# STM32_microcontroller_power.net
KiCad netlist of a schematic drawn in Altium Designer
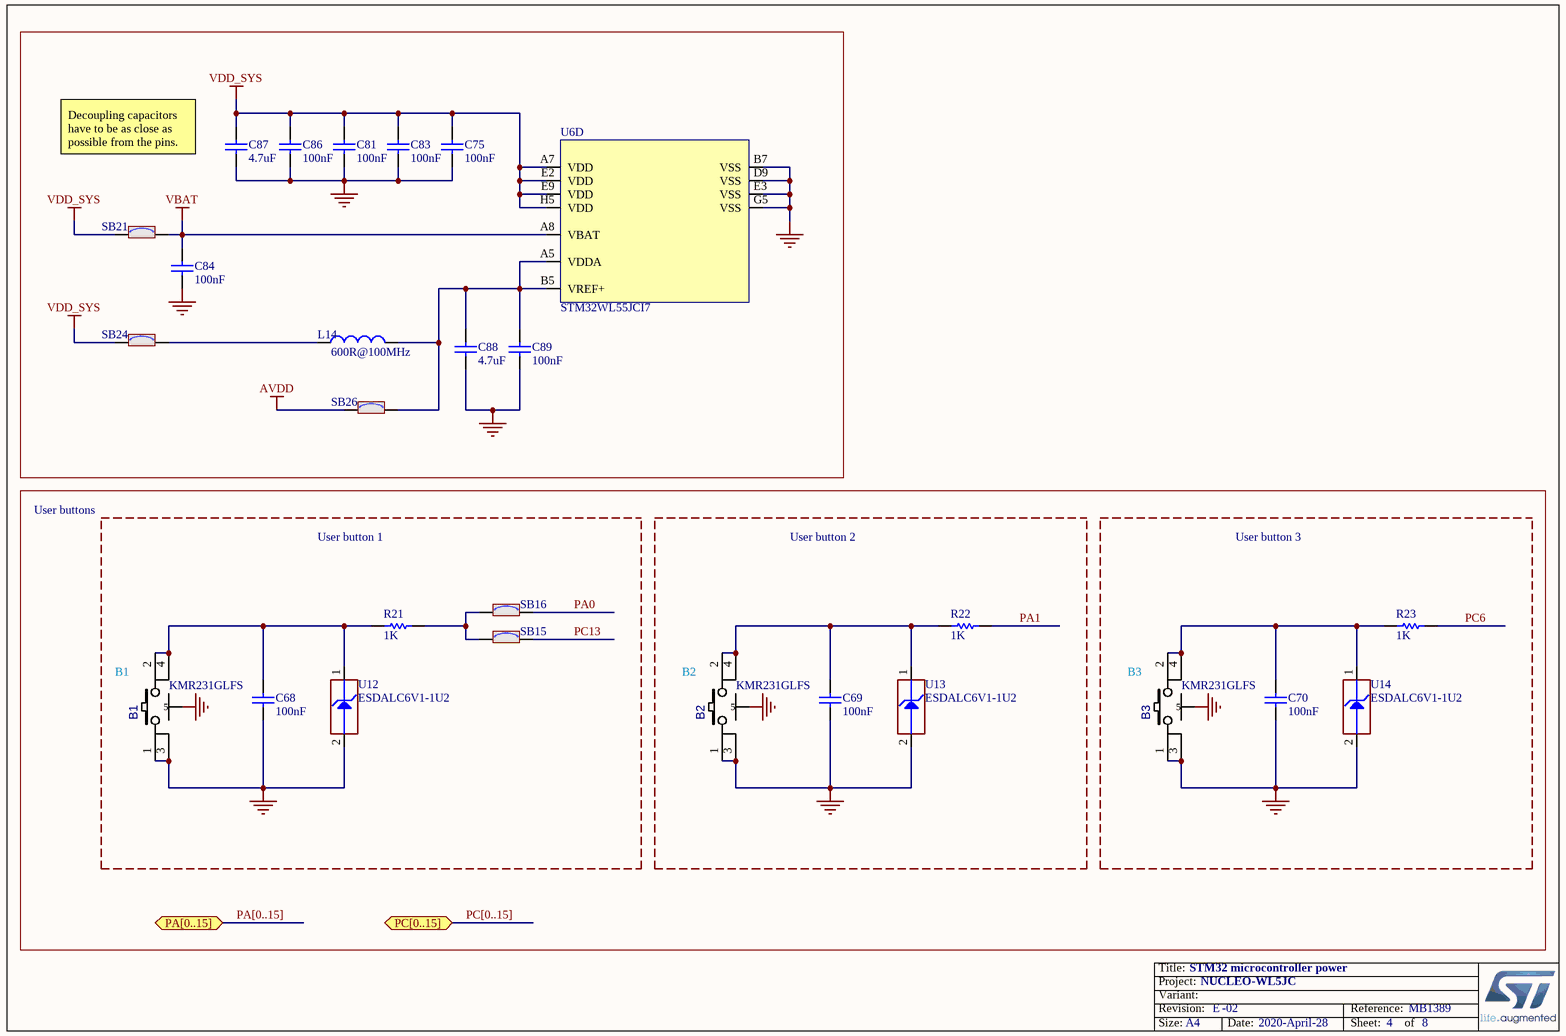
[diagram p0: STM32_microcontroller_power.SchDoc]

(export (version "E")
  (design (tool "Eeschema 10.0.6"))
  (components
    (comp (ref "B1")
      (value "KMR231GLFS")
      (footprint "SWI_C&K_Y78B23110FP__ITT_KMR231GLFS")
      (description "Microminiature Tact Switch for SMT - KMR 2 Series - 1.9 mm height")
      (fields
        (field (name "INTERNAL_PART_NUMBER") "MCD-01485")
        (field (name "MANUFACTURER") "C&K")
        (field (name "PROVIDED_BY") "SUBCO")
      )
      (libsource (lib "MCD_PARTS_database") (part "SW-PUSH-CMS_KMR2_BLACK"))
    )
    (comp (ref "B2")
      (value "KMR231GLFS")
      (footprint "SWI_C&K_Y78B23110FP__ITT_KMR231GLFS")
      (description "Microminiature Tact Switch for SMT - KMR 2 Series - 1.9 mm height")
      (fields
        (field (name "INTERNAL_PART_NUMBER") "MCD-01485")
        (field (name "MANUFACTURER") "C&K")
        (field (name "PROVIDED_BY") "SUBCO")
      )
      (libsource (lib "MCD_PARTS_database") (part "SW-PUSH-CMS_KMR2_BLACK"))
    )
    (comp (ref "B3")
      (value "KMR231GLFS")
      (footprint "SWI_C&K_Y78B23110FP__ITT_KMR231GLFS")
      (description "Microminiature Tact Switch for SMT - KMR 2 Series - 1.9 mm height")
      (fields
        (field (name "INTERNAL_PART_NUMBER") "MCD-01485")
        (field (name "MANUFACTURER") "C&K")
        (field (name "PROVIDED_BY") "SUBCO")
      )
      (libsource (lib "MCD_PARTS_database") (part "SW-PUSH-CMS_KMR2_BLACK"))
    )
    (comp (ref "C68")
      (value "100nF")
      (footprint "C0402")
      (description "Capacitor, MLCC, 100nF, 16V, X7R, 10%, 0402, T=0,5mm")
      (fields
        (field (name "INTERNAL_PART_NUMBER") "MCD-00102")
        (field (name "MANUFACTURER_PART_NUMBER") "CC0402KRX7R7BB104")
        (field (name "PROVIDED_BY") "SUBCO")
      )
      (libsource (lib "MCD_PARTS_database") (part "Capacitor"))
    )
    (comp (ref "C69")
      (value "100nF")
      (footprint "C0402")
      (description "Capacitor, MLCC, 100nF, 16V, X7R, 10%, 0402, T=0,5mm")
      (fields
        (field (name "INTERNAL_PART_NUMBER") "MCD-00102")
        (field (name "MANUFACTURER_PART_NUMBER") "CC0402KRX7R7BB104")
        (field (name "PROVIDED_BY") "SUBCO")
      )
      (libsource (lib "MCD_PARTS_database") (part "Capacitor"))
    )
    (comp (ref "C70")
      (value "100nF")
      (footprint "C0402")
      (description "Capacitor, MLCC, 100nF, 16V, X7R, 10%, 0402, T=0,5mm")
      (fields
        (field (name "INTERNAL_PART_NUMBER") "MCD-00102")
        (field (name "MANUFACTURER_PART_NUMBER") "CC0402KRX7R7BB104")
        (field (name "PROVIDED_BY") "SUBCO")
      )
      (libsource (lib "MCD_PARTS_database") (part "Capacitor"))
    )
    (comp (ref "C75")
      (value "100nF")
      (footprint "C0402")
      (description "Capacitor, MLCC, 100nF, 16V, X7R, 10%, 0402, T=0,5mm")
      (fields
        (field (name "INTERNAL_PART_NUMBER") "MCD-00102")
        (field (name "MANUFACTURER_PART_NUMBER") "CC0402KRX7R7BB104")
        (field (name "PROVIDED_BY") "SUBCO")
      )
      (libsource (lib "MCD_PARTS_database") (part "Capacitor"))
    )
    (comp (ref "C81")
      (value "100nF")
      (footprint "C0402")
      (description "Capacitor, MLCC, 100nF, 16V, X7R, 10%, 0402, T=0,5mm")
      (fields
        (field (name "INTERNAL_PART_NUMBER") "MCD-00102")
        (field (name "MANUFACTURER_PART_NUMBER") "CC0402KRX7R7BB104")
        (field (name "PROVIDED_BY") "SUBCO")
      )
      (libsource (lib "MCD_PARTS_database") (part "Capacitor"))
    )
    (comp (ref "C83")
      (value "100nF")
      (footprint "C0402")
      (description "Capacitor, MLCC, 100nF, 16V, X7R, 10%, 0402, T=0,5mm")
      (fields
        (field (name "INTERNAL_PART_NUMBER") "MCD-00102")
        (field (name "MANUFACTURER_PART_NUMBER") "CC0402KRX7R7BB104")
        (field (name "PROVIDED_BY") "SUBCO")
      )
      (libsource (lib "MCD_PARTS_database") (part "Capacitor"))
    )
    (comp (ref "C84")
      (value "100nF")
      (footprint "C0402")
      (description "Capacitor, MLCC, 100nF, 16V, X7R, 10%, 0402, T=0,5mm")
      (fields
        (field (name "INTERNAL_PART_NUMBER") "MCD-00102")
        (field (name "MANUFACTURER_PART_NUMBER") "CC0402KRX7R7BB104")
        (field (name "PROVIDED_BY") "SUBCO")
      )
      (libsource (lib "MCD_PARTS_database") (part "Capacitor"))
    )
    (comp (ref "C86")
      (value "100nF")
      (footprint "C0402")
      (description "Capacitor, MLCC, 100nF, 16V, X7R, 10%, 0402, T=0,5mm")
      (fields
        (field (name "INTERNAL_PART_NUMBER") "MCD-00102")
        (field (name "MANUFACTURER_PART_NUMBER") "CC0402KRX7R7BB104")
        (field (name "PROVIDED_BY") "SUBCO")
      )
      (libsource (lib "MCD_PARTS_database") (part "Capacitor"))
    )
    (comp (ref "C87")
      (value "4.7uF")
      (footprint "C0603")
      (description "Capacitor, MLCC, 4.7uF, 16V, X5R, 10%, 0603, T=0.8mm")
      (fields
        (field (name "INTERNAL_PART_NUMBER") "MCD-00009")
        (field (name "MANUFACTURER_PART_NUMBER") "CC0603KRX5R7BB475")
        (field (name "PROVIDED_BY") "SUBCO")
      )
      (libsource (lib "MCD_PARTS_database") (part "Capacitor"))
    )
    (comp (ref "C88")
      (value "4.7uF")
      (footprint "C0603")
      (description "Capacitor, MLCC, 4.7uF, 16V, X5R, 10%, 0603, T=0.8mm")
      (fields
        (field (name "INTERNAL_PART_NUMBER") "MCD-00009")
        (field (name "MANUFACTURER_PART_NUMBER") "CC0603KRX5R7BB475")
        (field (name "PROVIDED_BY") "SUBCO")
      )
      (libsource (lib "MCD_PARTS_database") (part "Capacitor"))
    )
    (comp (ref "C89")
      (value "100nF")
      (footprint "C0402")
      (description "Capacitor, MLCC, 100nF, 16V, X7R, 10%, 0402, T=0,5mm")
      (fields
        (field (name "INTERNAL_PART_NUMBER") "MCD-00102")
        (field (name "MANUFACTURER_PART_NUMBER") "CC0402KRX7R7BB104")
        (field (name "PROVIDED_BY") "SUBCO")
      )
      (libsource (lib "MCD_PARTS_database") (part "Capacitor"))
    )
    (comp (ref "L14")
      (value "600R@100MHz")
      (footprint "L0603")
      (description "SMD Chip ferrite bead, 600R@100MHz +/-25%, 350mA, 500mohm DC, 0603, T=0.8mm")
      (fields
        (field (name "INTERNAL_PART_NUMBER") "MCD-00047")
        (field (name "MANUFACTURER_PART_NUMBER") "FCM1608KF-601T03")
        (field (name "PROVIDED_BY") "SUBCO")
      )
      (libsource (lib "MCD_PARTS_database") (part "BEAD"))
    )
    (comp (ref "R21")
      (value "1K")
      (footprint "R0402")
      (description "Resistor,1K,0402,1%,1/16W")
      (fields
        (field (name "INTERNAL_PART_NUMBER") "MCD-00061")
        (field (name "MANUFACTURER_PART_NUMBER") "RC0402FR-071KL")
        (field (name "PROVIDED_BY") "SUBCO")
      )
      (libsource (lib "MCD_PARTS_database") (part "Resistor"))
    )
    (comp (ref "R22")
      (value "1K")
      (footprint "R0402")
      (description "Resistor,1K,0402,1%,1/16W")
      (fields
        (field (name "INTERNAL_PART_NUMBER") "MCD-00061")
        (field (name "MANUFACTURER_PART_NUMBER") "RC0402FR-071KL")
        (field (name "PROVIDED_BY") "SUBCO")
      )
      (libsource (lib "MCD_PARTS_database") (part "Resistor"))
    )
    (comp (ref "R23")
      (value "1K")
      (footprint "R0402")
      (description "Resistor,1K,0402,1%,1/16W")
      (fields
        (field (name "INTERNAL_PART_NUMBER") "MCD-00061")
        (field (name "MANUFACTURER_PART_NUMBER") "RC0402FR-071KL")
        (field (name "PROVIDED_BY") "SUBCO")
      )
      (libsource (lib "MCD_PARTS_database") (part "Resistor"))
    )
    (comp (ref "SB15")
      (value "~")
      (footprint "SOLDER-BRIDGE_R0603-0R")
      (description "Solder Bridge ON")
      (fields
        (field (name "INTERNAL_PART_NUMBER") "MCD-00071")
        (field (name "MANUFACTURER_PART_NUMBER") "RC0603JR-070RL")
        (field (name "PROVIDED_BY") "SUBCO")
      )
      (libsource (lib "MCD_PARTS_database") (part "SB_ON"))
    )
    (comp (ref "SB16")
      (value "~")
      (footprint "SOLDER-BRIDGE_R0603-0R")
      (description "Solder Bridge ON")
      (fields
        (field (name "INTERNAL_PART_NUMBER") "MCD-00071")
        (field (name "MANUFACTURER_PART_NUMBER") "RC0603JR-070RL")
        (field (name "PROVIDED_BY") "SUBCO")
      )
      (libsource (lib "MCD_PARTS_database") (part "SB_ON"))
    )
    (comp (ref "SB21")
      (value "~")
      (footprint "SOLDER-BRIDGE_R0603-0R")
      (description "Solder Bridge ON")
      (fields
        (field (name "INTERNAL_PART_NUMBER") "MCD-00071")
        (field (name "MANUFACTURER_PART_NUMBER") "RC0603JR-070RL")
        (field (name "PROVIDED_BY") "SUBCO")
      )
      (libsource (lib "MCD_PARTS_database") (part "SB_ON"))
    )
    (comp (ref "SB24")
      (value "~")
      (footprint "SOLDER-BRIDGE_R0603-0R")
      (description "Solder Bridge ON")
      (fields
        (field (name "INTERNAL_PART_NUMBER") "MCD-00071")
        (field (name "MANUFACTURER_PART_NUMBER") "RC0603JR-070RL")
        (field (name "PROVIDED_BY") "SUBCO")
      )
      (libsource (lib "MCD_PARTS_database") (part "SB_ON"))
    )
    (comp (ref "SB26")
      (value "~")
      (footprint "SOLDER-BRIDGE_R0603-0R")
      (description "Solder Bridge ON")
      (fields
        (field (name "INTERNAL_PART_NUMBER") "MCD-00071")
        (field (name "MANUFACTURER_PART_NUMBER") "RC0603JR-070RL")
        (field (name "PROVIDED_BY") "SUBCO")
      )
      (libsource (lib "MCD_PARTS_database") (part "SB_ON"))
    )
    (comp (ref "U6")
      (value "STM32WL55JCI7")
      (footprint "ICC_UFBGA73_5X5_P050")
      (description "Multiprotocol Wireless 32-bit MCUwith LPWAN Sub-GHz radio solution")
      (fields
        (field (name "INTERNAL_PART_NUMBER") "MCD-01435")
        (field (name "MANUFACTURER") "STMICROELECTRONICS")
      )
      (libsource (lib "MCD_PARTS_database") (part "STM32WL5x_BGA73"))
    )
    (comp (ref "U12")
      (value "ESDALC6V1-1U2")
      (footprint "ESD_ST0201")
      (description "ESD protection 6V1")
      (fields
        (field (name "INTERNAL_PART_NUMBER") "MCD-00170")
        (field (name "MANUFACTURER") "STMICROELECTRONICS")
        (field (name "PROVIDED_BY") "SUBCO with ST control")
      )
      (libsource (lib "MCD_PARTS_database") (part "ESD-TRANSIL"))
    )
    (comp (ref "U13")
      (value "ESDALC6V1-1U2")
      (footprint "ESD_ST0201")
      (description "ESD protection 6V1")
      (fields
        (field (name "INTERNAL_PART_NUMBER") "MCD-00170")
        (field (name "MANUFACTURER") "STMICROELECTRONICS")
        (field (name "PROVIDED_BY") "SUBCO with ST control")
      )
      (libsource (lib "MCD_PARTS_database") (part "ESD-TRANSIL"))
    )
    (comp (ref "U14")
      (value "ESDALC6V1-1U2")
      (footprint "ESD_ST0201")
      (description "ESD protection 6V1")
      (fields
        (field (name "INTERNAL_PART_NUMBER") "MCD-00170")
        (field (name "MANUFACTURER") "STMICROELECTRONICS")
        (field (name "PROVIDED_BY") "SUBCO with ST control")
      )
      (libsource (lib "MCD_PARTS_database") (part "ESD-TRANSIL"))
    )
  )
  (nets
    (net (code "29") (name "/PA0") (class "Default")
      (node (ref "SB16") (pin "2") (pinfunction "2_2") (pintype "passive"))
    )
    (net (code "30") (name "/PA1") (class "Default")
      (node (ref "R22") (pin "2") (pinfunction "2_2") (pintype "passive"))
    )
    (net (code "32") (name "/PC6") (class "Default")
      (node (ref "R23") (pin "2") (pinfunction "2_2") (pintype "passive"))
    )
    (net (code "33") (name "/PC13") (class "Default")
      (node (ref "SB15") (pin "2") (pinfunction "2_2") (pintype "passive"))
    )
    (net (code "35") (name "AVDD") (class "Default")
      (node (ref "SB26") (pin "1") (pinfunction "1_1") (pintype "passive"))
    )
    (net (code "36") (name "GND") (class "Default")
      (node (ref "B1") (pin "1") (pinfunction "1_1") (pintype "passive"))
      (node (ref "B1") (pin "3") (pinfunction "3_3") (pintype "passive"))
      (node (ref "B1") (pin "5") (pinfunction "5_5") (pintype "passive"))
      (node (ref "B2") (pin "1") (pinfunction "1_1") (pintype "passive"))
      (node (ref "B2") (pin "3") (pinfunction "3_3") (pintype "passive"))
      (node (ref "B2") (pin "5") (pinfunction "5_5") (pintype "passive"))
      (node (ref "B3") (pin "1") (pinfunction "1_1") (pintype "passive"))
      (node (ref "B3") (pin "3") (pinfunction "3_3") (pintype "passive"))
      (node (ref "B3") (pin "5") (pinfunction "5_5") (pintype "passive"))
      (node (ref "C68") (pin "1") (pinfunction "1_1") (pintype "passive"))
      (node (ref "C69") (pin "1") (pinfunction "1_1") (pintype "passive"))
      (node (ref "C70") (pin "1") (pinfunction "1_1") (pintype "passive"))
      (node (ref "C75") (pin "1") (pinfunction "1_1") (pintype "passive"))
      (node (ref "C81") (pin "1") (pinfunction "1_1") (pintype "passive"))
      (node (ref "C83") (pin "1") (pinfunction "1_1") (pintype "passive"))
      (node (ref "C84") (pin "1") (pinfunction "1_1") (pintype "passive"))
      (node (ref "C86") (pin "1") (pinfunction "1_1") (pintype "passive"))
      (node (ref "C87") (pin "1") (pinfunction "1_1") (pintype "passive"))
      (node (ref "C88") (pin "1") (pinfunction "1_1") (pintype "passive"))
      (node (ref "C89") (pin "1") (pinfunction "1_1") (pintype "passive"))
      (node (ref "U12") (pin "2") (pinfunction "GND_2") (pintype "passive"))
      (node (ref "U13") (pin "2") (pinfunction "GND_2") (pintype "passive"))
      (node (ref "U14") (pin "2") (pinfunction "GND_2") (pintype "passive"))
      (node (ref "U6") (pin "B7") (pinfunction "VSS_B7") (pintype "passive"))
      (node (ref "U6") (pin "D9") (pinfunction "VSS_D9") (pintype "passive"))
      (node (ref "U6") (pin "E3") (pinfunction "VSS_E3") (pintype "passive"))
      (node (ref "U6") (pin "G5") (pinfunction "VSS_G5") (pintype "passive"))
    )
    (net (code "37") (name "Net-(L14-Pad1)") (class "Default")
      (node (ref "L14") (pin "1") (pinfunction "1_1") (pintype "passive"))
      (node (ref "SB24") (pin "2") (pinfunction "2_2") (pintype "passive"))
    )
    (net (code "38") (name "Net-(R21-Pad2)") (class "Default")
      (node (ref "R21") (pin "2") (pinfunction "2_2") (pintype "passive"))
      (node (ref "SB15") (pin "1") (pinfunction "1_1") (pintype "passive"))
      (node (ref "SB16") (pin "1") (pinfunction "1_1") (pintype "passive"))
    )
    (net (code "39") (name "Net-(U6D-VDDA)") (class "Default")
      (node (ref "C88") (pin "2") (pinfunction "2_2") (pintype "passive"))
      (node (ref "C89") (pin "2") (pinfunction "2_2") (pintype "passive"))
      (node (ref "L14") (pin "2") (pinfunction "2_2") (pintype "passive"))
      (node (ref "SB26") (pin "2") (pinfunction "2_2") (pintype "passive"))
      (node (ref "U6") (pin "A5") (pinfunction "VDDA_A5") (pintype "passive"))
      (node (ref "U6") (pin "B5") (pinfunction "VREF+_B5") (pintype "passive"))
    )
    (net (code "40") (name "Net-(U12-IO1)") (class "Default")
      (node (ref "B1") (pin "2") (pinfunction "2_2") (pintype "passive"))
      (node (ref "B1") (pin "4") (pinfunction "4_4") (pintype "passive"))
      (node (ref "C68") (pin "2") (pinfunction "2_2") (pintype "passive"))
      (node (ref "R21") (pin "1") (pinfunction "1_1") (pintype "passive"))
      (node (ref "U12") (pin "1") (pinfunction "IO1_1") (pintype "passive"))
    )
    (net (code "41") (name "Net-(U13-IO1)") (class "Default")
      (node (ref "B2") (pin "2") (pinfunction "2_2") (pintype "passive"))
      (node (ref "B2") (pin "4") (pinfunction "4_4") (pintype "passive"))
      (node (ref "C69") (pin "2") (pinfunction "2_2") (pintype "passive"))
      (node (ref "R22") (pin "1") (pinfunction "1_1") (pintype "passive"))
      (node (ref "U13") (pin "1") (pinfunction "IO1_1") (pintype "passive"))
    )
    (net (code "42") (name "Net-(U14-IO1)") (class "Default")
      (node (ref "B3") (pin "2") (pinfunction "2_2") (pintype "passive"))
      (node (ref "B3") (pin "4") (pinfunction "4_4") (pintype "passive"))
      (node (ref "C70") (pin "2") (pinfunction "2_2") (pintype "passive"))
      (node (ref "R23") (pin "1") (pinfunction "1_1") (pintype "passive"))
      (node (ref "U14") (pin "1") (pinfunction "IO1_1") (pintype "passive"))
    )
    (net (code "43") (name "VBAT") (class "Default")
      (node (ref "C84") (pin "2") (pinfunction "2_2") (pintype "passive"))
      (node (ref "SB21") (pin "2") (pinfunction "2_2") (pintype "passive"))
      (node (ref "U6") (pin "A8") (pinfunction "VBAT_A8") (pintype "passive"))
    )
    (net (code "44") (name "VDD_SYS") (class "Default")
      (node (ref "C75") (pin "2") (pinfunction "2_2") (pintype "passive"))
      (node (ref "C81") (pin "2") (pinfunction "2_2") (pintype "passive"))
      (node (ref "C83") (pin "2") (pinfunction "2_2") (pintype "passive"))
      (node (ref "C86") (pin "2") (pinfunction "2_2") (pintype "passive"))
      (node (ref "C87") (pin "2") (pinfunction "2_2") (pintype "passive"))
      (node (ref "SB21") (pin "1") (pinfunction "1_1") (pintype "passive"))
      (node (ref "SB24") (pin "1") (pinfunction "1_1") (pintype "passive"))
      (node (ref "U6") (pin "A7") (pinfunction "VDD_A7") (pintype "passive"))
      (node (ref "U6") (pin "E2") (pinfunction "VDD_E2") (pintype "passive"))
      (node (ref "U6") (pin "E9") (pinfunction "VDD_E9") (pintype "passive"))
      (node (ref "U6") (pin "H5") (pinfunction "VDD_H5") (pintype "passive"))
    )
  )
)
